# main.net
KiCad netlist of a schematic drawn in EAGLE
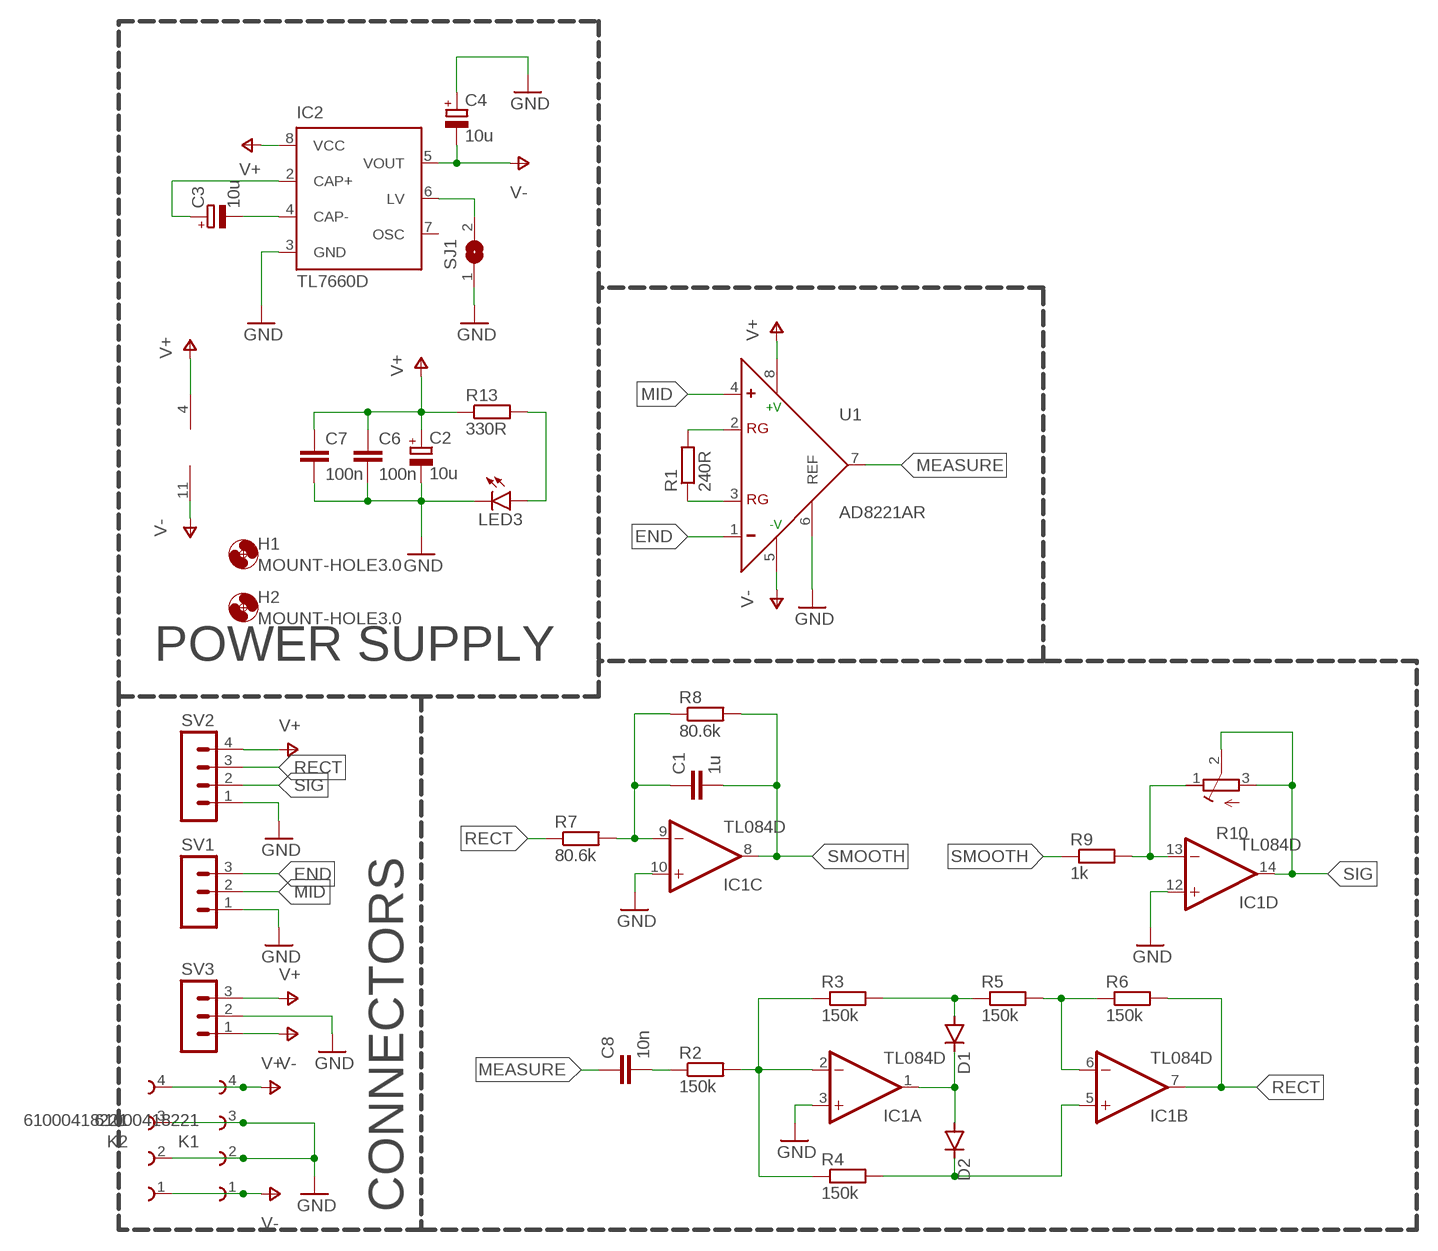
[diagram p0: schematic, sheet 1]

(export (version "E")
  (design (tool "Eeschema 10.0.6"))
  (components
    (comp (ref "C1")
      (value "1u")
      (footprint "eagle-import:C0805")
      (libsource (lib "eagle-import") (part "C-EUC0805"))
    )
    (comp (ref "C2")
      (value "10u")
      (footprint "eagle-import:SMC_B")
      (libsource (lib "eagle-import") (part "CPOL-EUSMCB"))
    )
    (comp (ref "C3")
      (value "10u")
      (footprint "eagle-import:SMC_B")
      (libsource (lib "eagle-import") (part "CPOL-EUSMCB"))
    )
    (comp (ref "C4")
      (value "10u")
      (footprint "eagle-import:SMC_B")
      (libsource (lib "eagle-import") (part "CPOL-EUSMCB"))
    )
    (comp (ref "C6")
      (value "100n")
      (footprint "eagle-import:C0805")
      (libsource (lib "eagle-import") (part "C-EUC0805"))
    )
    (comp (ref "C7")
      (value "100n")
      (footprint "eagle-import:C0805")
      (libsource (lib "eagle-import") (part "C-EUC0805"))
    )
    (comp (ref "C8")
      (value "10n")
      (footprint "eagle-import:C0805")
      (libsource (lib "eagle-import") (part "C-EUC0805"))
    )
    (comp (ref "D1")
      (value "DIODE-SOD80C")
      (footprint "eagle-import:SOD80C")
      (libsource (lib "eagle-import") (part "DIODE-SOD80C"))
    )
    (comp (ref "D2")
      (value "DIODE-SOD80C")
      (footprint "eagle-import:SOD80C")
      (libsource (lib "eagle-import") (part "DIODE-SOD80C"))
    )
    (comp (ref "H1")
      (value "MOUNT-HOLE3.0")
      (footprint "eagle-import:3,0")
      (libsource (lib "eagle-import") (part "MOUNT-HOLE3.0"))
    )
    (comp (ref "H2")
      (value "MOUNT-HOLE3.0")
      (footprint "eagle-import:3,0")
      (libsource (lib "eagle-import") (part "MOUNT-HOLE3.0"))
    )
    (comp (ref "IC1")
      (value "TL084D")
      (footprint "eagle-import:SO14")
      (libsource (lib "eagle-import") (part "TL084D"))
    )
    (comp (ref "IC2")
      (value "TL7660D")
      (footprint "eagle-import:D_R-PDSO-G08")
      (fields (field (name "MPN") "TL7660CD"))
      (libsource (lib "eagle-import") (part "TL7660D"))
    )
    (comp (ref "K1")
      (value "61000418221")
      (footprint "eagle-import:61000418221")
      (libsource (lib "eagle-import") (part "61000418221"))
    )
    (comp (ref "K2")
      (value "61000418221")
      (footprint "eagle-import:61000418221")
      (libsource (lib "eagle-import") (part "61000418221"))
    )
    (comp (ref "LED3")
      (value "LEDCHIP-LED0805")
      (footprint "eagle-import:CHIP-LED0805")
      (libsource (lib "eagle-import") (part "LEDCHIP-LED0805"))
    )
    (comp (ref "R1")
      (value "240R")
      (footprint "eagle-import:R1206")
      (libsource (lib "eagle-import") (part "R-EU_R1206"))
    )
    (comp (ref "R2")
      (value "150k")
      (footprint "eagle-import:R1206")
      (libsource (lib "eagle-import") (part "R-EU_R1206"))
    )
    (comp (ref "R3")
      (value "150k")
      (footprint "eagle-import:R1206")
      (libsource (lib "eagle-import") (part "R-EU_R1206"))
    )
    (comp (ref "R4")
      (value "150k")
      (footprint "eagle-import:R1206")
      (libsource (lib "eagle-import") (part "R-EU_R1206"))
    )
    (comp (ref "R5")
      (value "150k")
      (footprint "eagle-import:R1206")
      (libsource (lib "eagle-import") (part "R-EU_R1206"))
    )
    (comp (ref "R6")
      (value "150k")
      (footprint "eagle-import:R1206")
      (libsource (lib "eagle-import") (part "R-EU_R1206"))
    )
    (comp (ref "R7")
      (value "80.6k")
      (footprint "eagle-import:R1206")
      (libsource (lib "eagle-import") (part "R-EU_R1206"))
    )
    (comp (ref "R8")
      (value "80.6k")
      (footprint "eagle-import:R1206")
      (libsource (lib "eagle-import") (part "R-EU_R1206"))
    )
    (comp (ref "R9")
      (value "1k")
      (footprint "eagle-import:R1206")
      (libsource (lib "eagle-import") (part "R-EU_R1206"))
    )
    (comp (ref "R10")
      (value "R-TRIMM3314J")
      (footprint "eagle-import:RTRIM3314J")
      (libsource (lib "eagle-import") (part "R-TRIMM3314J"))
    )
    (comp (ref "R13")
      (value "330R")
      (footprint "eagle-import:R1206")
      (libsource (lib "eagle-import") (part "R-EU_R1206"))
    )
    (comp (ref "SJ1") (value "SJ") (footprint "eagle-import:SJ") (libsource (lib "eagle-import") (part "SJ")))
    (comp (ref "SV1")
      (value "MA03-1")
      (footprint "eagle-import:MA03-1")
      (libsource (lib "eagle-import") (part "MA03-1"))
    )
    (comp (ref "SV2")
      (value "MA04-1")
      (footprint "eagle-import:MA04-1")
      (libsource (lib "eagle-import") (part "MA04-1"))
    )
    (comp (ref "SV3")
      (value "MA03-1")
      (footprint "eagle-import:MA03-1")
      (libsource (lib "eagle-import") (part "MA03-1"))
    )
    (comp (ref "U1")
      (value "AD8221AR")
      (footprint "eagle-import:SO8")
      (libsource (lib "eagle-import") (part "AD8221AR"))
    )
  )
  (nets
    (net (code "1") (name "END") (class "Default")
      (node (ref "SV1") (pin "3") (pinfunction "3_3") (pintype "passive"))
      (node (ref "U1") (pin "1") (pinfunction "-_1") (pintype "input"))
    )
    (net (code "2") (name "GND") (class "Default")
      (node (ref "C2") (pin "-") (pinfunction "-_-") (pintype "passive"))
      (node (ref "C4") (pin "+") (pinfunction "+_+") (pintype "passive"))
      (node (ref "C6") (pin "2") (pinfunction "2_2") (pintype "passive"))
      (node (ref "C7") (pin "2") (pinfunction "2_2") (pintype "passive"))
      (node (ref "IC1") (pin "10") (pinfunction "+IN_10") (pintype "input"))
      (node (ref "IC1") (pin "12") (pinfunction "+IN_12") (pintype "input"))
      (node (ref "IC1") (pin "3") (pinfunction "+IN_3") (pintype "input"))
      (node (ref "IC2") (pin "3") (pinfunction "GND_3") (pintype "power_in"))
      (node (ref "K1") (pin "2") (pinfunction "2_2") (pintype "passive"))
      (node (ref "K1") (pin "3") (pinfunction "3_3") (pintype "passive"))
      (node (ref "K2") (pin "2") (pinfunction "2_2") (pintype "passive"))
      (node (ref "K2") (pin "3") (pinfunction "3_3") (pintype "passive"))
      (node (ref "LED3") (pin "C") (pinfunction "C_C") (pintype "passive"))
      (node (ref "SJ1") (pin "1") (pinfunction "1_1") (pintype "passive"))
      (node (ref "SV1") (pin "1") (pinfunction "1_1") (pintype "passive"))
      (node (ref "SV2") (pin "1") (pinfunction "1_1") (pintype "passive"))
      (node (ref "SV3") (pin "2") (pinfunction "2_2") (pintype "passive"))
      (node (ref "U1") (pin "6") (pinfunction "REF_6") (pintype "passive"))
    )
    (net (code "3") (name "MEASURE") (class "Default")
      (node (ref "C8") (pin "1") (pinfunction "1_1") (pintype "passive"))
      (node (ref "U1") (pin "7") (pinfunction "OUT_7") (pintype "output"))
    )
    (net (code "4") (name "MID") (class "Default")
      (node (ref "SV1") (pin "2") (pinfunction "2_2") (pintype "passive"))
      (node (ref "U1") (pin "4") (pinfunction "+_4") (pintype "input"))
    )
    (net (code "5") (name "Net-(C8-Pad2)") (class "Default")
      (node (ref "C8") (pin "2") (pinfunction "2_2") (pintype "passive"))
      (node (ref "R2") (pin "1") (pinfunction "1_1") (pintype "passive"))
    )
    (net (code "6") (name "Net-(D1-PadA)") (class "Default")
      (node (ref "D1") (pin "A") (pinfunction "A_A") (pintype "passive"))
      (node (ref "R3") (pin "2") (pinfunction "2_2") (pintype "passive"))
      (node (ref "R5") (pin "1") (pinfunction "1_1") (pintype "passive"))
    )
    (net (code "7") (name "Net-(IC1A--IN)") (class "Default")
      (node (ref "IC1") (pin "2") (pinfunction "-IN_2") (pintype "input"))
      (node (ref "R2") (pin "2") (pinfunction "2_2") (pintype "passive"))
      (node (ref "R3") (pin "1") (pinfunction "1_1") (pintype "passive"))
      (node (ref "R4") (pin "1") (pinfunction "1_1") (pintype "passive"))
    )
    (net (code "8") (name "Net-(IC1A-OUT)") (class "Default")
      (node (ref "D1") (pin "C") (pinfunction "C_C") (pintype "passive"))
      (node (ref "D2") (pin "A") (pinfunction "A_A") (pintype "passive"))
      (node (ref "IC1") (pin "1") (pinfunction "OUT_1") (pintype "output"))
    )
    (net (code "9") (name "Net-(IC1B-+IN)") (class "Default")
      (node (ref "D2") (pin "C") (pinfunction "C_C") (pintype "passive"))
      (node (ref "IC1") (pin "5") (pinfunction "+IN_5") (pintype "input"))
      (node (ref "R4") (pin "2") (pinfunction "2_2") (pintype "passive"))
    )
    (net (code "10") (name "Net-(IC1B--IN)") (class "Default")
      (node (ref "IC1") (pin "6") (pinfunction "-IN_6") (pintype "input"))
      (node (ref "R5") (pin "2") (pinfunction "2_2") (pintype "passive"))
      (node (ref "R6") (pin "1") (pinfunction "1_1") (pintype "passive"))
    )
    (net (code "11") (name "Net-(IC1C--IN)") (class "Default")
      (node (ref "C1") (pin "1") (pinfunction "1_1") (pintype "passive"))
      (node (ref "IC1") (pin "9") (pinfunction "-IN_9") (pintype "input"))
      (node (ref "R7") (pin "2") (pinfunction "2_2") (pintype "passive"))
      (node (ref "R8") (pin "1") (pinfunction "1_1") (pintype "passive"))
    )
    (net (code "12") (name "Net-(IC1D--IN)") (class "Default")
      (node (ref "IC1") (pin "13") (pinfunction "-IN_13") (pintype "input"))
      (node (ref "R10") (pin "1") (pinfunction "E_1") (pintype "passive"))
      (node (ref "R9") (pin "2") (pinfunction "2_2") (pintype "passive"))
    )
    (net (code "13") (name "Net-(IC2-CAP+)") (class "Default")
      (node (ref "C3") (pin "+") (pinfunction "+_+") (pintype "passive"))
      (node (ref "IC2") (pin "2") (pinfunction "CAP+_2") (pintype "passive"))
    )
    (net (code "14") (name "Net-(IC2-CAP-)") (class "Default")
      (node (ref "C3") (pin "-") (pinfunction "-_-") (pintype "passive"))
      (node (ref "IC2") (pin "4") (pinfunction "CAP-_4") (pintype "passive"))
    )
    (net (code "15") (name "Net-(IC2-LV)") (class "Default")
      (node (ref "IC2") (pin "6") (pinfunction "LV_6") (pintype "passive"))
      (node (ref "SJ1") (pin "2") (pinfunction "2_2") (pintype "passive"))
    )
    (net (code "16") (name "Net-(LED3-PadA)") (class "Default")
      (node (ref "LED3") (pin "A") (pinfunction "A_A") (pintype "passive"))
      (node (ref "R13") (pin "2") (pinfunction "2_2") (pintype "passive"))
    )
    (net (code "17") (name "Net-(R1-Pad1)") (class "Default")
      (node (ref "R1") (pin "1") (pinfunction "1_1") (pintype "passive"))
      (node (ref "U1") (pin "3") (pinfunction "RG_3") (pintype "passive"))
    )
    (net (code "18") (name "Net-(R1-Pad2)") (class "Default")
      (node (ref "R1") (pin "2") (pinfunction "2_2") (pintype "passive"))
      (node (ref "U1") (pin "2") (pinfunction "RG_2") (pintype "passive"))
    )
    (net (code "19") (name "RECT") (class "Default")
      (node (ref "IC1") (pin "7") (pinfunction "OUT_7") (pintype "output"))
      (node (ref "R6") (pin "2") (pinfunction "2_2") (pintype "passive"))
      (node (ref "R7") (pin "1") (pinfunction "1_1") (pintype "passive"))
      (node (ref "SV2") (pin "3") (pinfunction "3_3") (pintype "passive"))
    )
    (net (code "20") (name "SIG") (class "Default")
      (node (ref "IC1") (pin "14") (pinfunction "OUT_14") (pintype "output"))
      (node (ref "R10") (pin "2") (pinfunction "S_2") (pintype "passive"))
      (node (ref "R10") (pin "3") (pinfunction "A_3") (pintype "passive"))
      (node (ref "SV2") (pin "2") (pinfunction "2_2") (pintype "passive"))
    )
    (net (code "21") (name "SMOOTH") (class "Default")
      (node (ref "C1") (pin "2") (pinfunction "2_2") (pintype "passive"))
      (node (ref "IC1") (pin "8") (pinfunction "OUT_8") (pintype "output"))
      (node (ref "R8") (pin "2") (pinfunction "2_2") (pintype "passive"))
      (node (ref "R9") (pin "1") (pinfunction "1_1") (pintype "passive"))
    )
    (net (code "22") (name "V+") (class "Default")
      (node (ref "C2") (pin "+") (pinfunction "+_+") (pintype "passive"))
      (node (ref "C6") (pin "1") (pinfunction "1_1") (pintype "passive"))
      (node (ref "C7") (pin "1") (pinfunction "1_1") (pintype "passive"))
      (node (ref "IC1") (pin "4") (pinfunction "V+_4") (pintype "power_in"))
      (node (ref "IC2") (pin "8") (pinfunction "VCC_8") (pintype "power_in"))
      (node (ref "K1") (pin "4") (pinfunction "4_4") (pintype "passive"))
      (node (ref "K2") (pin "4") (pinfunction "4_4") (pintype "passive"))
      (node (ref "R13") (pin "1") (pinfunction "1_1") (pintype "passive"))
      (node (ref "SV2") (pin "4") (pinfunction "4_4") (pintype "passive"))
      (node (ref "SV3") (pin "3") (pinfunction "3_3") (pintype "passive"))
      (node (ref "U1") (pin "8") (pinfunction "+V_8") (pintype "power_in"))
    )
    (net (code "23") (name "V-") (class "Default")
      (node (ref "C4") (pin "-") (pinfunction "-_-") (pintype "passive"))
      (node (ref "IC1") (pin "11") (pinfunction "V-_11") (pintype "power_in"))
      (node (ref "IC2") (pin "5") (pinfunction "VOUT_5") (pintype "passive"))
      (node (ref "K1") (pin "1") (pinfunction "1_1") (pintype "passive"))
      (node (ref "K2") (pin "1") (pinfunction "1_1") (pintype "passive"))
      (node (ref "SV3") (pin "1") (pinfunction "1_1") (pintype "passive"))
      (node (ref "U1") (pin "5") (pinfunction "-V_5") (pintype "power_in"))
    )
    (net (code "24") (name "unconnected-(IC2-OSC-Pad7)") (class "Default")
      (node (ref "IC2") (pin "7") (pinfunction "OSC_7") (pintype "input"))
    )
  )
)
